# battery.net
KiCad netlist of a schematic drawn in EAGLE
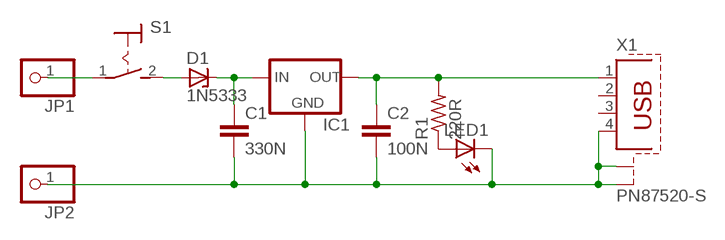
[diagram p0: schematic, sheet 1]

(export (version "E")
  (design (tool "Eeschema 10.0.6"))
  (components
    (comp (ref "C1")
      (value "330N")
      (footprint "eagle-import:C025-025X050")
      (libsource (lib "eagle-import") (part "C-EU025-025X050"))
    )
    (comp (ref "C2")
      (value "100N")
      (footprint "eagle-import:C025-025X050")
      (libsource (lib "eagle-import") (part "C-EU025-025X050"))
    )
    (comp (ref "D1")
      (value "1N5333")
      (footprint "eagle-import:C1702-15")
      (libsource (lib "eagle-import") (part "1N5333"))
    )
    (comp (ref "IC1")
      (value "78MXXS")
      (footprint "eagle-import:78MXXS")
      (libsource (lib "eagle-import") (part "78MXXS"))
    )
    (comp (ref "JP1")
      (value "PINHD-1X1")
      (footprint "eagle-import:1X01")
      (libsource (lib "eagle-import") (part "PINHD-1X1"))
    )
    (comp (ref "JP2")
      (value "PINHD-1X1")
      (footprint "eagle-import:1X01")
      (libsource (lib "eagle-import") (part "PINHD-1X1"))
    )
    (comp (ref "LED1")
      (value "LED3MM")
      (footprint "eagle-import:LED3MM")
      (libsource (lib "eagle-import") (part "LED3MM"))
    )
    (comp (ref "R1")
      (value "220R")
      (footprint "eagle-import:0414_15")
      (libsource (lib "eagle-import") (part "R-US_0414/15"))
    )
    (comp (ref "S1")
      (value "MS243")
      (footprint "eagle-import:MS243")
      (libsource (lib "eagle-import") (part "MS243"))
    )
    (comp (ref "X1")
      (value "PN87520-S")
      (footprint "eagle-import:PN87520-S")
      (libsource (lib "eagle-import") (part "PN87520-S"))
    )
  )
  (nets
    (net (code "1") (name "Net-(C1-Pad1)") (class "Default")
      (node (ref "C1") (pin "1") (pinfunction "1_1") (pintype "passive"))
      (node (ref "D1") (pin "C") (pinfunction "C_C") (pintype "passive"))
      (node (ref "IC1") (pin "IN") (pinfunction "IN_IN") (pintype "input"))
    )
    (net (code "2") (name "Net-(C2-Pad1)") (class "Default")
      (node (ref "C2") (pin "1") (pinfunction "1_1") (pintype "passive"))
      (node (ref "IC1") (pin "OUT") (pinfunction "OUT_OUT") (pintype "passive"))
      (node (ref "R1") (pin "2") (pinfunction "2_2") (pintype "passive"))
      (node (ref "X1") (pin "1") (pinfunction "1_1") (pintype "passive"))
    )
    (net (code "3") (name "Net-(LED1-C)") (class "Default")
      (node (ref "C1") (pin "2") (pinfunction "2_2") (pintype "passive"))
      (node (ref "C2") (pin "2") (pinfunction "2_2") (pintype "passive"))
      (node (ref "IC1") (pin "GND") (pinfunction "GND_GND") (pintype "input"))
      (node (ref "JP2") (pin "1") (pinfunction "1_1") (pintype "passive"))
      (node (ref "LED1") (pin "K") (pinfunction "C_K") (pintype "passive"))
      (node (ref "X1") (pin "4") (pinfunction "4_4") (pintype "passive"))
      (node (ref "X1") (pin "S1") (pinfunction "S1_S1") (pintype "passive"))
      (node (ref "X1") (pin "S2") (pinfunction "S2_S2") (pintype "passive"))
    )
    (net (code "4") (name "Net-(LED1-PadA)") (class "Default")
      (node (ref "LED1") (pin "A") (pinfunction "A_A") (pintype "passive"))
      (node (ref "R1") (pin "1") (pinfunction "1_1") (pintype "passive"))
    )
    (net (code "5") (name "Net-(S1-P)") (class "Default")
      (node (ref "JP1") (pin "1") (pinfunction "1_1") (pintype "passive"))
      (node (ref "S1") (pin "1") (pinfunction "P_1") (pintype "passive"))
    )
    (net (code "6") (name "Net-(S1-S)") (class "Default")
      (node (ref "D1") (pin "A") (pinfunction "A_A") (pintype "passive"))
      (node (ref "S1") (pin "2") (pinfunction "S_2") (pintype "passive"))
    )
    (net (code "7") (name "unconnected-(X1-Pad2)") (class "Default")
      (node (ref "X1") (pin "2") (pinfunction "2_2") (pintype "passive"))
    )
    (net (code "8") (name "unconnected-(X1-Pad3)") (class "Default")
      (node (ref "X1") (pin "3") (pinfunction "3_3") (pintype "passive"))
    )
  )
)
